# PCB_RX.net
KiCad netlist of a schematic drawn in Altium Designer
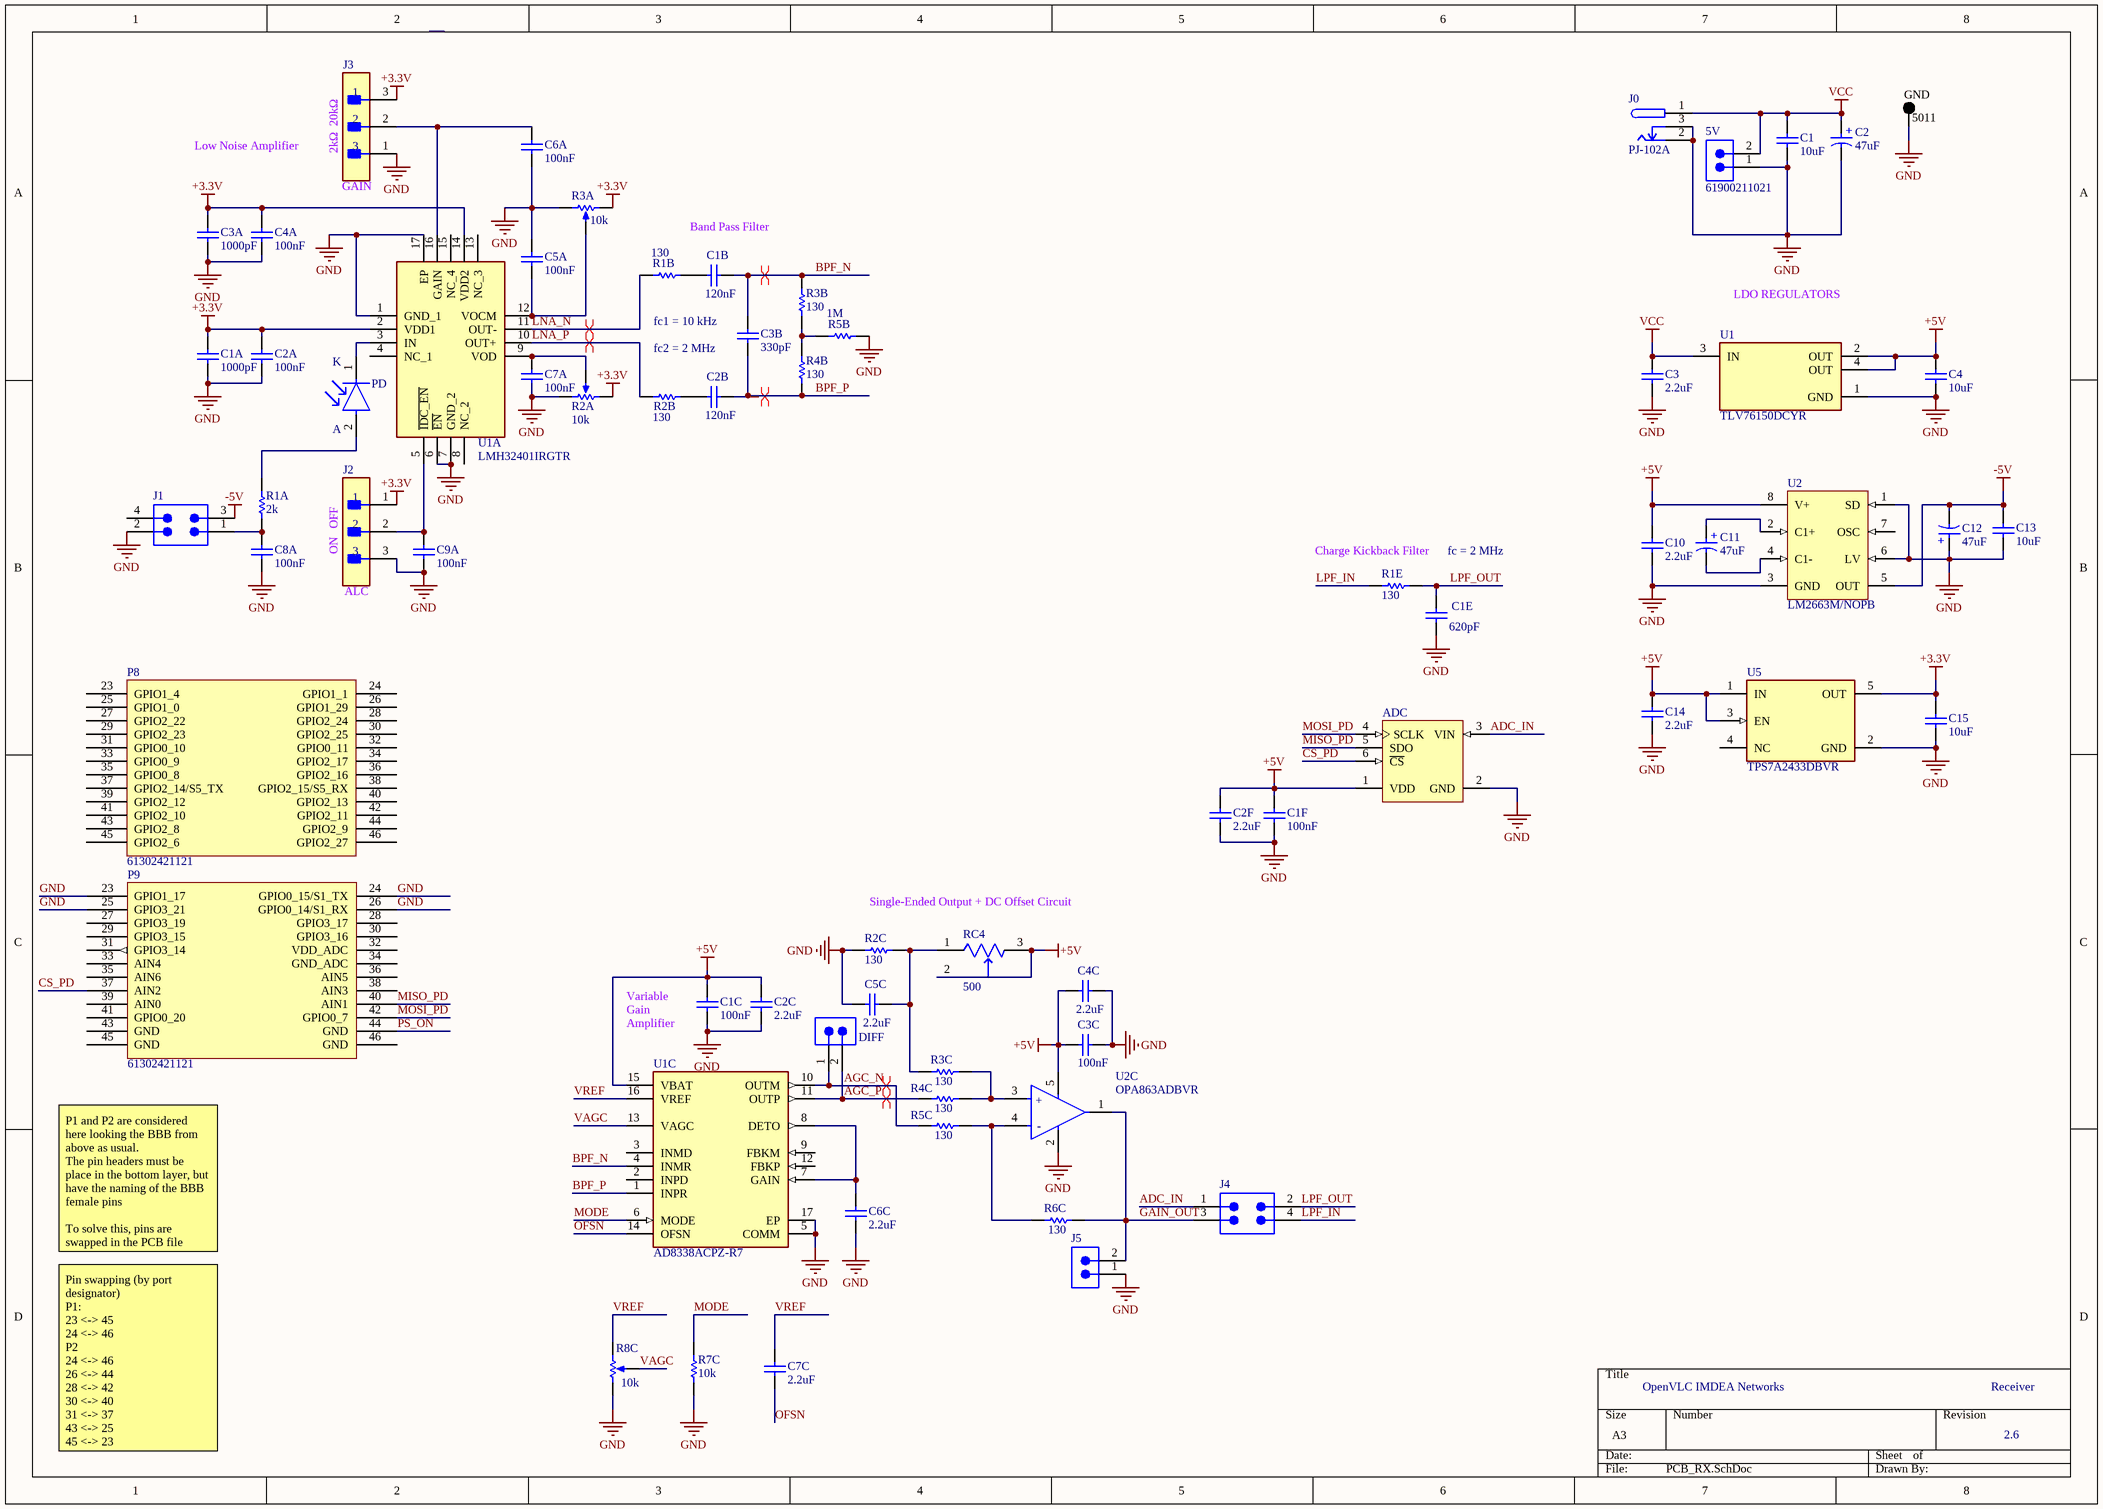
[diagram p0: PCB_RX.SchDoc]

(export (version "E")
  (design (tool "Eeschema 10.0.6"))
  (components
    (comp (ref "5V")
      (value "61900211021")
      (footprint "61900211021")
      (libsource (lib "Altium Content Vault") (part "Header_Male_1R_02P"))
    )
    (comp (ref "ADC")
      (value "ADS7886SBDBVR")
      (footprint "TI-DBV6_M")
      (fields (field (name "MANUFACTURER") "Texas Instruments"))
      (libsource (lib "Altium Content Vault") (part "TI-ADS788XDXX6"))
    )
    (comp (ref "C1")
      (value "10uF")
      (footprint "RESC1608X55N")
      (description "Capacitor")
      (fields (field (name "Comment") "Cap") (field (name "PUBLISHER") "Altium Limited"))
      (libsource (lib "Miscellaneous Devices") (part "Cap"))
    )
    (comp (ref "C1A")
      (value "1000pF")
      (footprint "RESC1608X55N")
      (description "Capacitor")
      (fields (field (name "Comment") "Cap") (field (name "PUBLISHER") "Altium Limited"))
      (libsource (lib "Miscellaneous Devices") (part "Cap"))
    )
    (comp (ref "C1B")
      (value "120nF")
      (footprint "RESC1608X55N")
      (description "Capacitor")
      (fields (field (name "Comment") "Cap") (field (name "PUBLISHER") "Altium Limited"))
      (libsource (lib "Miscellaneous Devices") (part "Cap"))
    )
    (comp (ref "C1C")
      (value "100nF")
      (footprint "RESC1608X55N")
      (description "Capacitor")
      (fields (field (name "Comment") "Cap") (field (name "PUBLISHER") "Altium Limited"))
      (libsource (lib "Miscellaneous Devices") (part "Cap"))
    )
    (comp (ref "C1E")
      (value "620pF")
      (footprint "RESC1608X55N")
      (description "Capacitor")
      (fields (field (name "Comment") "Cap") (field (name "PUBLISHER") "Altium Limited"))
      (libsource (lib "Miscellaneous Devices") (part "Cap"))
    )
    (comp (ref "C1F")
      (value "100nF")
      (footprint "RESC1608X55N")
      (description "Capacitor")
      (fields (field (name "Comment") "Cap") (field (name "PUBLISHER") "Altium Limited"))
      (libsource (lib "Miscellaneous Devices") (part "Cap"))
    )
    (comp (ref "C2")
      (value "47uF")
      (footprint "WCAP-PSLP_D5H5.5")
      (description "875105242006 WCAP-PSLP Aluminum Polymer Capacitors")
      (fields (field (name "TOLERANCE") "20%"))
      (libsource (lib "Altium Content Vault") (part "Capacitor_Polarized"))
    )
    (comp (ref "C2A")
      (value "100nF")
      (footprint "RESC1608X55N")
      (description "Capacitor")
      (fields (field (name "Comment") "Cap") (field (name "PUBLISHER") "Altium Limited"))
      (libsource (lib "Miscellaneous Devices") (part "Cap"))
    )
    (comp (ref "C2B")
      (value "120nF")
      (footprint "RESC1608X55N")
      (description "Capacitor")
      (fields (field (name "Comment") "Cap") (field (name "PUBLISHER") "Altium Limited"))
      (libsource (lib "Miscellaneous Devices") (part "Cap"))
    )
    (comp (ref "C2C")
      (value "2.2uF")
      (footprint "RESC1608X55N")
      (description "Capacitor")
      (fields (field (name "Comment") "Cap") (field (name "PUBLISHER") "Altium Limited"))
      (libsource (lib "Miscellaneous Devices") (part "Cap"))
    )
    (comp (ref "C2F")
      (value "2.2uF")
      (footprint "RESC1608X55N")
      (description "Capacitor")
      (fields (field (name "Comment") "Cap") (field (name "PUBLISHER") "Altium Limited"))
      (libsource (lib "Miscellaneous Devices") (part "Cap"))
    )
    (comp (ref "C3")
      (value "2.2uF")
      (footprint "RESC1608X55N")
      (description "Capacitor")
      (fields (field (name "Comment") "Cap") (field (name "PUBLISHER") "Altium Limited"))
      (libsource (lib "Miscellaneous Devices") (part "Cap"))
    )
    (comp (ref "C3A")
      (value "1000pF")
      (footprint "RESC1608X55N")
      (description "Capacitor")
      (fields (field (name "Comment") "Cap") (field (name "PUBLISHER") "Altium Limited"))
      (libsource (lib "Miscellaneous Devices") (part "Cap"))
    )
    (comp (ref "C3B")
      (value "330pF")
      (footprint "RESC1608X55N")
      (description "Capacitor")
      (fields (field (name "Comment") "Cap") (field (name "PUBLISHER") "Altium Limited"))
      (libsource (lib "Miscellaneous Devices") (part "Cap"))
    )
    (comp (ref "C3C")
      (value "100nF")
      (footprint "RESC1608X55N")
      (description "Capacitor")
      (fields (field (name "Comment") "Cap") (field (name "PUBLISHER") "Altium Limited"))
      (libsource (lib "Miscellaneous Devices") (part "Cap"))
    )
    (comp (ref "C4")
      (value "10uF")
      (footprint "RESC1608X55N")
      (description "Capacitor")
      (fields (field (name "Comment") "Cap") (field (name "PUBLISHER") "Altium Limited"))
      (libsource (lib "Miscellaneous Devices") (part "Cap"))
    )
    (comp (ref "C4A")
      (value "100nF")
      (footprint "RESC1608X55N")
      (description "Capacitor")
      (fields (field (name "Comment") "Cap") (field (name "PUBLISHER") "Altium Limited"))
      (libsource (lib "Miscellaneous Devices") (part "Cap"))
    )
    (comp (ref "C4C")
      (value "2.2uF")
      (footprint "RESC1608X55N")
      (description "Capacitor")
      (fields (field (name "Comment") "Cap") (field (name "PUBLISHER") "Altium Limited"))
      (libsource (lib "Miscellaneous Devices") (part "Cap"))
    )
    (comp (ref "C5A")
      (value "100nF")
      (footprint "RESC1608X55N")
      (description "Capacitor")
      (fields (field (name "Comment") "Cap") (field (name "PUBLISHER") "Altium Limited"))
      (libsource (lib "Miscellaneous Devices") (part "Cap"))
    )
    (comp (ref "C5C")
      (value "2.2uF")
      (footprint "RESC1608X55N")
      (description "Capacitor")
      (fields (field (name "Comment") "Cap") (field (name "PUBLISHER") "Altium Limited"))
      (libsource (lib "Miscellaneous Devices") (part "Cap"))
    )
    (comp (ref "C6A")
      (value "100nF")
      (footprint "RESC1608X55N")
      (description "Capacitor")
      (fields (field (name "Comment") "Cap") (field (name "PUBLISHER") "Altium Limited"))
      (libsource (lib "Miscellaneous Devices") (part "Cap"))
    )
    (comp (ref "C6C")
      (value "2.2uF")
      (footprint "RESC1608X55N")
      (description "Capacitor")
      (fields (field (name "Comment") "Cap") (field (name "PUBLISHER") "Altium Limited"))
      (libsource (lib "Miscellaneous Devices") (part "Cap"))
    )
    (comp (ref "C7A")
      (value "100nF")
      (footprint "RESC1608X55N")
      (description "Capacitor")
      (fields (field (name "Comment") "Cap") (field (name "PUBLISHER") "Altium Limited"))
      (libsource (lib "Miscellaneous Devices") (part "Cap"))
    )
    (comp (ref "C7C")
      (value "2.2uF")
      (footprint "RESC1608X55N")
      (description "Capacitor")
      (fields (field (name "Comment") "Cap") (field (name "PUBLISHER") "Altium Limited"))
      (libsource (lib "Miscellaneous Devices") (part "Cap"))
    )
    (comp (ref "C8A")
      (value "100nF")
      (footprint "RESC1608X55N")
      (description "Capacitor")
      (fields (field (name "Comment") "Cap") (field (name "PUBLISHER") "Altium Limited"))
      (libsource (lib "Miscellaneous Devices") (part "Cap"))
    )
    (comp (ref "C9A")
      (value "100nF")
      (footprint "RESC1608X55N")
      (description "Capacitor")
      (fields (field (name "Comment") "Cap") (field (name "PUBLISHER") "Altium Limited"))
      (libsource (lib "Miscellaneous Devices") (part "Cap"))
    )
    (comp (ref "C10")
      (value "2.2uF")
      (footprint "RESC1608X55N")
      (description "Capacitor")
      (fields (field (name "Comment") "Cap") (field (name "PUBLISHER") "Altium Limited"))
      (libsource (lib "Miscellaneous Devices") (part "Cap"))
    )
    (comp (ref "C11")
      (value "47uF")
      (footprint "WCAP-PSLP_D5H5.5")
      (description "875105242006 WCAP-PSLP Aluminum Polymer Capacitors")
      (fields (field (name "TOLERANCE") "20%"))
      (libsource (lib "Altium Content Vault") (part "Capacitor_Polarized"))
    )
    (comp (ref "C12")
      (value "47uF")
      (footprint "WCAP-PSLP_D5H5.5")
      (description "875105242006 WCAP-PSLP Aluminum Polymer Capacitors")
      (fields (field (name "TOLERANCE") "20%"))
      (libsource (lib "Altium Content Vault") (part "Capacitor_Polarized"))
    )
    (comp (ref "C13")
      (value "10uF")
      (footprint "RESC1608X55N")
      (description "Capacitor")
      (fields (field (name "Comment") "Cap") (field (name "PUBLISHER") "Altium Limited"))
      (libsource (lib "Miscellaneous Devices") (part "Cap"))
    )
    (comp (ref "C14")
      (value "2.2uF")
      (footprint "RESC1608X55N")
      (description "Capacitor")
      (fields (field (name "Comment") "GRM188R6YA475KE15D") (field (name "PUBLISHER") "Altium Limited"))
      (libsource (lib "Miscellaneous Devices") (part "Cap"))
    )
    (comp (ref "C15")
      (value "10uF")
      (footprint "RESC1608X55N")
      (description "Capacitor")
      (fields (field (name "Comment") "GRM188R6YA106MA73D") (field (name "PUBLISHER") "Altium Limited"))
      (libsource (lib "Miscellaneous Devices") (part "Cap"))
    )
    (comp (ref "DIFF")
      (value "61300211121")
      (footprint "61300211121")
      (libsource (lib "Altium Content Vault") (part "Header_Male_1R_02P"))
    )
    (comp (ref "GND")
      (value "5011")
      (footprint "KSTN-5011_V")
      (description "Test Point, Black, Through Hole, RoHS, Bulk")
      (fields (field (name "MANUFACTURER") "Keystone"))
      (libsource (lib "Altium Content Vault") (part "TESTPOINT_BLACK"))
    )
    (comp (ref "J0")
      (value "PJ-102A")
      (footprint "FP-PJ-102A-MFG")
      (description "PJ-102A 2.0 x 6.5 mm, 2.5 A, Horizontal, Through Hole, Tapered Pins, Dc Power Jack Connector")
      (libsource (lib "Altium Content Vault") (part "c639f672d24b5d70918fa8d934b95d1"))
    )
    (comp (ref "J1")
      (value "62200421121")
      (footprint "62200421121")
      (libsource (lib "Altium Content Vault") (part "Header_Male_2R_04P"))
    )
    (comp (ref "J2")
      (value "GRPB031VWVN-RC")
      (footprint "FP-TMS-103-02-G-S-MFG")
      (description "CONN HEADER VERT 3POS 1.27MM")
      (libsource (lib "") (part "0d3f023dd272f625e17a2be33dea85f_1"))
    )
    (comp (ref "J3")
      (value "61300311121")
      (footprint "FP-TMS-103-02-G-S-MFG")
      (description "CONN HEADER VERT 3POS 1.27MM")
      (libsource (lib "Altium Content Vault") (part "0d3f023dd272f625e17a2be33dea85f"))
    )
    (comp (ref "J4")
      (value "61300421121")
      (footprint "61300421121")
      (libsource (lib "Altium Content Vault") (part "Header_Male_2R_04P"))
    )
    (comp (ref "J5")
      (value "61900211121")
      (footprint "61900211121")
      (libsource (lib "Altium Content Vault") (part "Header_Male_1R_02P"))
    )
    (comp (ref "P8")
      (value "61302421121")
      (footprint "BBB_CAPE_NO_HEADER_R_24")
      (libsource (lib "BeagleBoneCape") (part "BBB_P8_reduced"))
    )
    (comp (ref "P9")
      (value "61302421121")
      (footprint "BBB_CAPE_NO_HEADER_R_24")
      (libsource (lib "BeagleBoneCape") (part "BBB_P9_reduced"))
    )
    (comp (ref "PD")
      (value "SFH213")
      (footprint "FP-SFH213-0")
      (description "SENSOR PHOTODIODE 850NM RADIAL")
      (fields (field (name "MANUFACTURER") "OSRAM") (field (name "VOLTAGE") "50V"))
      (libsource (lib "Altium Content Vault") (part "9b7c99953c265a88c20b8f1023d9605"))
    )
    (comp (ref "R1A")
      (value "2k")
      (footprint "RESC1608X55N")
      (description "Resistor")
      (fields (field (name "Comment") "Res1") (field (name "PUBLISHER") "Altium Limited"))
      (libsource (lib "Miscellaneous Devices") (part "Res1"))
    )
    (comp (ref "R1B")
      (value "130")
      (footprint "RESC1608X55N")
      (description "Resistor")
      (fields (field (name "Comment") "Res1") (field (name "PUBLISHER") "Altium Limited"))
      (libsource (lib "Miscellaneous Devices") (part "Res1"))
    )
    (comp (ref "R1E")
      (value "130")
      (footprint "RESC1608X55N")
      (description "Resistor")
      (fields (field (name "Comment") "Res1") (field (name "PUBLISHER") "Altium Limited"))
      (libsource (lib "Miscellaneous Devices") (part "Res1"))
    )
    (comp (ref "R2A")
      (value "10k")
      (footprint "BOUR-3362P")
      (description "Square Trimpot(R) Trimming Potentiometer, 10 KOhm, 300 V, -55 to 125 degC, 3-Pin THD, RoHS, Tube")
      (fields (field (name "TOLERANCE") "1%"))
      (libsource (lib "Altium Content Vault") (part "RES-POT-3"))
    )
    (comp (ref "R2B")
      (value "130")
      (footprint "RESC1608X55N")
      (description "Resistor")
      (fields (field (name "Comment") "Res1") (field (name "PUBLISHER") "Altium Limited"))
      (libsource (lib "Miscellaneous Devices") (part "Res1"))
    )
    (comp (ref "R2C")
      (value "130")
      (footprint "RESC1608X55N")
      (description "Resistor")
      (fields (field (name "Comment") "Res1") (field (name "PUBLISHER") "Altium Limited"))
      (libsource (lib "Miscellaneous Devices") (part "Res1"))
    )
    (comp (ref "R3A")
      (value "10k")
      (footprint "BOUR-3362P")
      (description "Square Trimpot(R) Trimming Potentiometer, 10 KOhm, 300 V, -55 to 125 degC, 3-Pin THD, RoHS, Tube")
      (fields (field (name "TOLERANCE") "1%"))
      (libsource (lib "Altium Content Vault") (part "RES-POT-3"))
    )
    (comp (ref "R3B")
      (value "130")
      (footprint "RESC1608X55N")
      (description "Resistor")
      (fields (field (name "Comment") "500") (field (name "PUBLISHER") "Altium Limited"))
      (libsource (lib "Miscellaneous Devices") (part "Res1"))
    )
    (comp (ref "R3C")
      (value "130")
      (footprint "RESC1608X55N")
      (description "Resistor")
      (fields (field (name "Comment") "Res1") (field (name "PUBLISHER") "Altium Limited"))
      (libsource (lib "Miscellaneous Devices") (part "Res1"))
    )
    (comp (ref "R4B")
      (value "130")
      (footprint "RESC1608X55N")
      (description "Resistor")
      (fields (field (name "Comment") "Res1") (field (name "PUBLISHER") "Altium Limited"))
      (libsource (lib "Miscellaneous Devices") (part "Res1"))
    )
    (comp (ref "R4C")
      (value "130")
      (footprint "RESC1608X55N")
      (description "Resistor")
      (fields (field (name "Comment") "Res1") (field (name "PUBLISHER") "Altium Limited"))
      (libsource (lib "Miscellaneous Devices") (part "Res1"))
    )
    (comp (ref "R5B")
      (value "1M")
      (footprint "RESC1608X55N")
      (description "Resistor")
      (fields (field (name "Comment") "Res1") (field (name "PUBLISHER") "Altium Limited"))
      (libsource (lib "Miscellaneous Devices") (part "Res1"))
    )
    (comp (ref "R5C")
      (value "130")
      (footprint "RESC1608X55N")
      (description "Resistor")
      (fields (field (name "Comment") "Res1") (field (name "PUBLISHER") "Altium Limited"))
      (libsource (lib "Miscellaneous Devices") (part "Res1"))
    )
    (comp (ref "R6C")
      (value "130")
      (footprint "RESC1608X55N")
      (description "Resistor")
      (fields (field (name "Comment") "Res1") (field (name "PUBLISHER") "Altium Limited"))
      (libsource (lib "Miscellaneous Devices") (part "Res1"))
    )
    (comp (ref "R7C")
      (value "10k")
      (footprint "RESC1608X55N")
      (description "Resistor")
      (fields (field (name "Comment") "Res1") (field (name "PUBLISHER") "Altium Limited"))
      (libsource (lib "Miscellaneous Devices") (part "Res1"))
    )
    (comp (ref "R8C")
      (value "10k")
      (footprint "BOUR-3362P")
      (description "Square Trimpot(R) Trimming Potentiometer, 10 KOhm, 300 V, -55 to 125 degC, 3-Pin THD, RoHS, Tube")
      (fields (field (name "TOLERANCE") "1%"))
      (libsource (lib "Altium Content Vault") (part "RES-POT-3"))
    )
    (comp (ref "RC4")
      (value "500")
      (footprint "FP-3296W-MFG")
      (description "TRIMMER 500K OHM 0.5W PC PIN TOP")
      (fields
        (field (name "MANUFACTURER") "Bourns")
        (field (name "OCTOPART") "https://octopart.com/3296w-1-504lf-bourns-143884")
      )
      (libsource (lib "Altium Content Vault") (part "8d460c8a6f7ec10b1759d1b9c49aa93"))
    )
    (comp (ref "U1")
      (value "TLV76150DCYR")
      (footprint "FP-DCY0004A-MFG")
      (description "TLV76150DCYR 1-A 16-V high-PSRR linear voltage regulator 4-SOT-223 -40 to 125")
      (libsource (lib "Altium Content Vault") (part "991ffb903c51cf6179ce9942c0606aa"))
    )
    (comp (ref "U1A")
      (value "LMH32401IRGTR")
      (footprint "QFN50P300X300X100-17N-D")
      (fields (field (name "MOUSER PART NUMBER") "595-LMH32401IRGTR"))
      (libsource (lib "LMH32401IRGTR") (part "LMH32401IRGTR"))
    )
    (comp (ref "U1C")
      (value "AD8338ACPZ-R7")
      (footprint "FP-CP-16-22-IPC_A")
      (description "IC OPAMP VGA 1 CIRCUIT 16LFCSP")
      (fields
        (field (name "OCTOPART") "https://octopart.com/ad8338acpz-r7-analog+devices-21054770")
        (field (name "MANUFACTURER") "Analog Devices")
      )
      (libsource (lib "Altium Content Vault") (part "4ce7887af0b7713ffabab50ab6d8fb3"))
    )
    (comp (ref "U2")
      (value "LM2663M/NOPB")
      (footprint "D0008A_N")
      (description "Switched Capacitor Voltage Converter, 8-pin Narrow SOIC, Pb-Free")
      (fields (field (name "MANUFACTURER") "Texas Instruments"))
      (libsource (lib "Altium Content Vault") (part "PM-CHP-LM2661M-8"))
    )
    (comp (ref "U2C")
      (value "OPA863ADBVR")
      (footprint "FP-DBV0005A-MFG")
      (libsource (lib "Altium Content Vault") (part "4cd2dec86d87e6d90761bbce91e6ba3"))
    )
    (comp (ref "U5")
      (value "TPS7A2433DBVR")
      (footprint "FP-DBV0005A-MFG")
      (libsource (lib "Altium Content Vault") (part "ee7747973c1ed1d4cccbb20406fa51c"))
    )
  )
  (nets
    (net (code "1") (name "+3.3V") (class "Default")
      (node (ref "C15") (pin "2") (pinfunction "2_2") (pintype "passive"))
      (node (ref "C1A") (pin "1") (pinfunction "1_1") (pintype "passive"))
      (node (ref "C2A") (pin "1") (pinfunction "1_1") (pintype "passive"))
      (node (ref "C3A") (pin "1") (pinfunction "1_1") (pintype "passive"))
      (node (ref "C4A") (pin "1") (pinfunction "1_1") (pintype "passive"))
      (node (ref "J2") (pin "1") (pinfunction "1_1") (pintype "passive"))
      (node (ref "J3") (pin "3") (pinfunction "3_3") (pintype "passive"))
      (node (ref "R2A") (pin "1") (pinfunction "CCW_1") (pintype "passive"))
      (node (ref "R3A") (pin "3") (pinfunction "CW_3") (pintype "passive"))
      (node (ref "U1A") (pin "14") (pinfunction "VDD2_14") (pintype "passive"))
      (node (ref "U1A") (pin "2") (pinfunction "VDD1_2") (pintype "passive"))
      (node (ref "U5") (pin "5") (pinfunction "OUT_5") (pintype "power_in"))
    )
    (net (code "2") (name "+5V") (class "Default")
      (node (ref "ADC") (pin "1") (pinfunction "VDD_1") (pintype "power_in"))
      (node (ref "C10") (pin "2") (pinfunction "2_2") (pintype "passive"))
      (node (ref "C14") (pin "2") (pinfunction "2_2") (pintype "passive"))
      (node (ref "C1C") (pin "1") (pinfunction "1_1") (pintype "passive"))
      (node (ref "C1F") (pin "1") (pinfunction "1_1") (pintype "passive"))
      (node (ref "C2C") (pin "1") (pinfunction "1_1") (pintype "passive"))
      (node (ref "C2F") (pin "1") (pinfunction "1_1") (pintype "passive"))
      (node (ref "C3C") (pin "1") (pinfunction "1_1") (pintype "passive"))
      (node (ref "C4") (pin "2") (pinfunction "2_2") (pintype "passive"))
      (node (ref "C4C") (pin "1") (pinfunction "1_1") (pintype "passive"))
      (node (ref "RC4") (pin "2") (pinfunction "WIPER_2") (pintype "passive"))
      (node (ref "RC4") (pin "3") (pinfunction "CW_3") (pintype "passive"))
      (node (ref "U1") (pin "2") (pinfunction "OUT_2") (pintype "passive"))
      (node (ref "U1") (pin "4") (pinfunction "OUT_4") (pintype "passive"))
      (node (ref "U1C") (pin "15") (pinfunction "VBAT_15") (pintype "power_in"))
      (node (ref "U2") (pin "8") (pinfunction "V+_8") (pintype "power_in"))
      (node (ref "U2C") (pin "5") (pinfunction "VS+_5") (pintype "power_in"))
      (node (ref "U5") (pin "1") (pinfunction "IN_1") (pintype "power_in"))
      (node (ref "U5") (pin "3") (pinfunction "EN_3") (pintype "input"))
    )
    (net (code "3") (name "-5V") (class "Default")
      (node (ref "C12") (pin "2") (pinfunction "N_2") (pintype "passive"))
      (node (ref "C13") (pin "2") (pinfunction "2_2") (pintype "passive"))
      (node (ref "J1") (pin "3") (pinfunction "3_3") (pintype "passive"))
      (node (ref "U2") (pin "5") (pinfunction "OUT_5") (pintype "power_in"))
    )
    (net (code "4") (name "/ADC_IN") (class "Default")
      (node (ref "ADC") (pin "3") (pinfunction "VIN_3") (pintype "input"))
      (node (ref "J4") (pin "1") (pinfunction "1_1") (pintype "passive"))
    )
    (net (code "5") (name "/AGC_N") (class "Default")
      (node (ref "DIFF") (pin "1") (pinfunction "1_1") (pintype "passive"))
      (node (ref "R5C") (pin "2") (pinfunction "2_2") (pintype "passive"))
      (node (ref "U1C") (pin "10") (pinfunction "OUTM_10") (pintype "output"))
    )
    (net (code "6") (name "/AGC_P") (class "Default")
      (node (ref "DIFF") (pin "2") (pinfunction "2_2") (pintype "passive"))
      (node (ref "R4C") (pin "2") (pinfunction "2_2") (pintype "passive"))
      (node (ref "U1C") (pin "11") (pinfunction "OUTP_11") (pintype "output"))
    )
    (net (code "7") (name "/BPF_N") (class "Default")
      (node (ref "C1B") (pin "2") (pinfunction "2_2") (pintype "passive"))
      (node (ref "C3B") (pin "2") (pinfunction "2_2") (pintype "passive"))
      (node (ref "R3B") (pin "1") (pinfunction "1_1") (pintype "passive"))
      (node (ref "U1C") (pin "4") (pinfunction "INMR_4") (pintype "passive"))
    )
    (net (code "8") (name "/BPF_P") (class "Default")
      (node (ref "C2B") (pin "2") (pinfunction "2_2") (pintype "passive"))
      (node (ref "C3B") (pin "1") (pinfunction "1_1") (pintype "passive"))
      (node (ref "R4B") (pin "2") (pinfunction "2_2") (pintype "passive"))
      (node (ref "U1C") (pin "1") (pinfunction "INPR_1") (pintype "passive"))
    )
    (net (code "9") (name "/CS_PD") (class "Default")
      (node (ref "ADC") (pin "6") (pinfunction "~{CS}_6") (pintype "input"))
      (node (ref "P9") (pin "37") (pinfunction "AIN2_37") (pintype "passive"))
    )
    (net (code "10") (name "/GAIN_OUT") (class "Default")
      (node (ref "J4") (pin "3") (pinfunction "3_3") (pintype "passive"))
      (node (ref "J5") (pin "2") (pinfunction "2_2") (pintype "passive"))
      (node (ref "R6C") (pin "1") (pinfunction "1_1") (pintype "passive"))
      (node (ref "U2C") (pin "1") (pinfunction "VOUT_1") (pintype "passive"))
    )
    (net (code "11") (name "/LNA_N") (class "Default")
      (node (ref "R1B") (pin "2") (pinfunction "2_2") (pintype "passive"))
      (node (ref "U1A") (pin "11") (pinfunction "OUT-_11") (pintype "passive"))
    )
    (net (code "12") (name "/LNA_P") (class "Default")
      (node (ref "R2B") (pin "2") (pinfunction "2_2") (pintype "passive"))
      (node (ref "U1A") (pin "10") (pinfunction "OUT+_10") (pintype "passive"))
    )
    (net (code "13") (name "/LPF_IN") (class "Default")
      (node (ref "J4") (pin "4") (pinfunction "4_4") (pintype "passive"))
      (node (ref "R1E") (pin "2") (pinfunction "2_2") (pintype "passive"))
    )
    (net (code "14") (name "/LPF_OUT") (class "Default")
      (node (ref "C1E") (pin "1") (pinfunction "1_1") (pintype "passive"))
      (node (ref "J4") (pin "2") (pinfunction "2_2") (pintype "passive"))
      (node (ref "R1E") (pin "1") (pinfunction "1_1") (pintype "passive"))
    )
    (net (code "15") (name "/MISO_PD") (class "Default")
      (node (ref "ADC") (pin "5") (pinfunction "SDO_5") (pintype "tri_state"))
      (node (ref "P9") (pin "40") (pinfunction "AIN1_40") (pintype "passive"))
    )
    (net (code "16") (name "/MODE") (class "Default")
      (node (ref "R7C") (pin "2") (pinfunction "2_2") (pintype "passive"))
      (node (ref "U1C") (pin "6") (pinfunction "MODE_6") (pintype "input"))
    )
    (net (code "17") (name "/MOSI_PD") (class "Default")
      (node (ref "ADC") (pin "4") (pinfunction "SCLK_4") (pintype "input"))
      (node (ref "P9") (pin "42") (pinfunction "GPIO0_7_42") (pintype "passive"))
    )
    (net (code "18") (name "/OFSN") (class "Default")
      (node (ref "C7C") (pin "1") (pinfunction "1_1") (pintype "passive"))
      (node (ref "U1C") (pin "14") (pinfunction "OFSN_14") (pintype "passive"))
    )
    (net (code "19") (name "/PS_ON") (class "Default")
      (node (ref "P9") (pin "44") (pinfunction "GND_44") (pintype "passive"))
    )
    (net (code "20") (name "/VAGC") (class "Default")
      (node (ref "R8C") (pin "2") (pinfunction "S_2") (pintype "passive"))
      (node (ref "U1C") (pin "13") (pinfunction "VAGC_13") (pintype "power_in"))
    )
    (net (code "21") (name "/VREF") (class "Default")
      (node (ref "C7C") (pin "2") (pinfunction "2_2") (pintype "passive"))
      (node (ref "R8C") (pin "3") (pinfunction "CW_3") (pintype "passive"))
      (node (ref "U1C") (pin "16") (pinfunction "VREF_16") (pintype "power_in"))
    )
    (net (code "22") (name "GND") (class "Default")
      (node (ref "5V") (pin "1") (pinfunction "1_1") (pintype "passive"))
      (node (ref "ADC") (pin "2") (pinfunction "GND_2") (pintype "power_in"))
      (node (ref "C1") (pin "2") (pinfunction "2_2") (pintype "passive"))
      (node (ref "C10") (pin "1") (pinfunction "1_1") (pintype "passive"))
      (node (ref "C12") (pin "1") (pinfunction "P_1") (pintype "passive"))
      (node (ref "C13") (pin "1") (pinfunction "1_1") (pintype "passive"))
      (node (ref "C14") (pin "1") (pinfunction "1_1") (pintype "passive"))
      (node (ref "C15") (pin "1") (pinfunction "1_1") (pintype "passive"))
      (node (ref "C1A") (pin "2") (pinfunction "2_2") (pintype "passive"))
      (node (ref "C1C") (pin "2") (pinfunction "2_2") (pintype "passive"))
      (node (ref "C1E") (pin "2") (pinfunction "2_2") (pintype "passive"))
      (node (ref "C1F") (pin "2") (pinfunction "2_2") (pintype "passive"))
      (node (ref "C2") (pin "2") (pinfunction "N_2") (pintype "passive"))
      (node (ref "C2A") (pin "2") (pinfunction "2_2") (pintype "passive"))
      (node (ref "C2C") (pin "2") (pinfunction "2_2") (pintype "passive"))
      (node (ref "C2F") (pin "2") (pinfunction "2_2") (pintype "passive"))
      (node (ref "C3") (pin "1") (pinfunction "1_1") (pintype "passive"))
      (node (ref "C3A") (pin "2") (pinfunction "2_2") (pintype "passive"))
      (node (ref "C3C") (pin "2") (pinfunction "2_2") (pintype "passive"))
      (node (ref "C4") (pin "1") (pinfunction "1_1") (pintype "passive"))
      (node (ref "C4A") (pin "2") (pinfunction "2_2") (pintype "passive"))
      (node (ref "C4C") (pin "2") (pinfunction "2_2") (pintype "passive"))
      (node (ref "C5A") (pin "1") (pinfunction "1_1") (pintype "passive"))
      (node (ref "C5C") (pin "1") (pinfunction "1_1") (pintype "passive"))
      (node (ref "C6A") (pin "2") (pinfunction "2_2") (pintype "passive"))
      (node (ref "C6C") (pin "1") (pinfunction "1_1") (pintype "passive"))
      (node (ref "C7A") (pin "2") (pinfunction "2_2") (pintype "passive"))
      (node (ref "C8A") (pin "1") (pinfunction "1_1") (pintype "passive"))
      (node (ref "C9A") (pin "2") (pinfunction "2_2") (pintype "passive"))
      (node (ref "GND") (pin "1") (pinfunction "1_1") (pintype "passive"))
      (node (ref "J0") (pin "2") (pinfunction "2_2") (pintype "passive"))
      (node (ref "J0") (pin "3") (pinfunction "3_3") (pintype "passive"))
      (node (ref "J1") (pin "2") (pinfunction "2_2") (pintype "passive"))
      (node (ref "J2") (pin "3") (pinfunction "3_3") (pintype "passive"))
      (node (ref "J3") (pin "1") (pinfunction "1_1") (pintype "passive"))
      (node (ref "J5") (pin "1") (pinfunction "1_1") (pintype "passive"))
      (node (ref "P9") (pin "23") (pinfunction "GPIO1_17_23") (pintype "passive"))
      (node (ref "P9") (pin "24") (pinfunction "GPIO0_15/S1_TX_24") (pintype "passive"))
      (node (ref "P9") (pin "25") (pinfunction "GPIO3_21_25") (pintype "passive"))
      (node (ref "P9") (pin "26") (pinfunction "GPIO0_14/S1_RX_26") (pintype "passive"))
      (node (ref "R2A") (pin "3") (pinfunction "CW_3") (pintype "passive"))
      (node (ref "R2C") (pin "2") (pinfunction "2_2") (pintype "passive"))
      (node (ref "R3A") (pin "1") (pinfunction "CCW_1") (pintype "passive"))
      (node (ref "R5B") (pin "1") (pinfunction "1_1") (pintype "passive"))
      (node (ref "R7C") (pin "1") (pinfunction "1_1") (pintype "passive"))
      (node (ref "R8C") (pin "1") (pinfunction "CCW_1") (pintype "passive"))
      (node (ref "U1") (pin "1") (pinfunction "GND_1") (pintype "power_in"))
      (node (ref "U1A") (pin "1") (pinfunction "GND_1_1") (pintype "passive"))
      (node (ref "U1A") (pin "17") (pinfunction "EP_17") (pintype "passive"))
      (node (ref "U1A") (pin "6") (pinfunction "~{EN}_6") (pintype "passive"))
      (node (ref "U1A") (pin "7") (pinfunction "GND_2_7") (pintype "passive"))
      (node (ref "U1C") (pin "17") (pinfunction "EP_17") (pintype "power_in"))
      (node (ref "U1C") (pin "5") (pinfunction "COMM_5") (pintype "power_in"))
      (node (ref "U2") (pin "1") (pinfunction "SD_1") (pintype "input"))
      (node (ref "U2") (pin "3") (pinfunction "GND_3") (pintype "power_in"))
      (node (ref "U2") (pin "6") (pinfunction "LV_6") (pintype "input"))
      (node (ref "U2C") (pin "2") (pinfunction "VS-_2") (pintype "power_in"))
      (node (ref "U5") (pin "2") (pinfunction "GND_2") (pintype "power_in"))
    )
    (net (code "23") (name "Net-(C1B-Pad1)") (class "Default")
      (node (ref "C1B") (pin "1") (pinfunction "1_1") (pintype "passive"))
      (node (ref "R1B") (pin "1") (pinfunction "1_1") (pintype "passive"))
    )
    (net (code "24") (name "Net-(C2B-Pad1)") (class "Default")
      (node (ref "C2B") (pin "1") (pinfunction "1_1") (pintype "passive"))
      (node (ref "R2B") (pin "1") (pinfunction "1_1") (pintype "passive"))
    )
    (net (code "25") (name "Net-(C8A-Pad2)") (class "Default")
      (node (ref "C8A") (pin "2") (pinfunction "2_2") (pintype "passive"))
      (node (ref "J1") (pin "1") (pinfunction "1_1") (pintype "passive"))
      (node (ref "R1A") (pin "2") (pinfunction "2_2") (pintype "passive"))
    )
    (net (code "26") (name "Net-(C11-N)") (class "Default")
      (node (ref "C11") (pin "2") (pinfunction "N_2") (pintype "passive"))
      (node (ref "U2") (pin "4") (pinfunction "C1-_4") (pintype "input"))
    )
    (net (code "27") (name "Net-(C11-P)") (class "Default")
      (node (ref "C11") (pin "1") (pinfunction "P_1") (pintype "passive"))
      (node (ref "U2") (pin "2") (pinfunction "C1+_2") (pintype "input"))
    )
    (net (code "28") (name "Net-(PD-A)") (class "Default")
      (node (ref "PD") (pin "2") (pinfunction "A_2") (pintype "passive"))
      (node (ref "R1A") (pin "1") (pinfunction "1_1") (pintype "passive"))
    )
    (net (code "29") (name "Net-(PD-C)") (class "Default")
      (node (ref "PD") (pin "1") (pinfunction "C_1") (pintype "passive"))
      (node (ref "U1A") (pin "3") (pinfunction "IN_3") (pintype "passive"))
    )
    (net (code "30") (name "Net-(R2A-S)") (class "Default")
      (node (ref "C7A") (pin "1") (pinfunction "1_1") (pintype "passive"))
      (node (ref "R2A") (pin "2") (pinfunction "S_2") (pintype "passive"))
      (node (ref "U1A") (pin "9") (pinfunction "VOD_9") (pintype "passive"))
    )
    (net (code "31") (name "Net-(R3A-S)") (class "Default")
      (node (ref "C5A") (pin "2") (pinfunction "2_2") (pintype "passive"))
      (node (ref "R3A") (pin "2") (pinfunction "S_2") (pintype "passive"))
      (node (ref "U1A") (pin "12") (pinfunction "VOCM_12") (pintype "passive"))
    )
    (net (code "32") (name "Net-(R3B-Pad2)") (class "Default")
      (node (ref "R3B") (pin "2") (pinfunction "2_2") (pintype "passive"))
      (node (ref "R4B") (pin "1") (pinfunction "1_1") (pintype "passive"))
      (node (ref "R5B") (pin "2") (pinfunction "2_2") (pintype "passive"))
    )
    (net (code "33") (name "Net-(RC4-CCW)") (class "Default")
      (node (ref "C5C") (pin "2") (pinfunction "2_2") (pintype "passive"))
      (node (ref "R2C") (pin "1") (pinfunction "1_1") (pintype "passive"))
      (node (ref "R3C") (pin "2") (pinfunction "2_2") (pintype "passive"))
      (node (ref "RC4") (pin "1") (pinfunction "CCW_1") (pintype "passive"))
    )
    (net (code "34") (name "Net-(U1A-GAIN)") (class "Default")
      (node (ref "C6A") (pin "1") (pinfunction "1_1") (pintype "passive"))
      (node (ref "J3") (pin "2") (pinfunction "2_2") (pintype "passive"))
      (node (ref "U1A") (pin "16") (pinfunction "GAIN_16") (pintype "passive"))
    )
    (net (code "35") (name "Net-(U1A-~{IDC_EN})") (class "Default")
      (node (ref "C9A") (pin "1") (pinfunction "1_1") (pintype "passive"))
      (node (ref "J2") (pin "2") (pinfunction "2_2") (pintype "passive"))
      (node (ref "U1A") (pin "5") (pinfunction "~{IDC_EN}_5") (pintype "passive"))
    )
    (net (code "36") (name "Net-(U1C-DETO)") (class "Default")
      (node (ref "C6C") (pin "2") (pinfunction "2_2") (pintype "passive"))
      (node (ref "U1C") (pin "7") (pinfunction "GAIN_7") (pintype "input"))
      (node (ref "U1C") (pin "8") (pinfunction "DETO_8") (pintype "output"))
    )
    (net (code "37") (name "Net-(U2C-VIN+)") (class "Default")
      (node (ref "R3C") (pin "1") (pinfunction "1_1") (pintype "passive"))
      (node (ref "R4C") (pin "1") (pinfunction "1_1") (pintype "passive"))
      (node (ref "U2C") (pin "3") (pinfunction "VIN+_3") (pintype "tri_state"))
    )
    (net (code "38") (name "Net-(U2C-VIN-)") (class "Default")
      (node (ref "R5C") (pin "1") (pinfunction "1_1") (pintype "passive"))
      (node (ref "R6C") (pin "2") (pinfunction "2_2") (pintype "passive"))
      (node (ref "U2C") (pin "4") (pinfunction "VIN-_4") (pintype "tri_state"))
    )
    (net (code "39") (name "VCC") (class "Default")
      (node (ref "5V") (pin "2") (pinfunction "2_2") (pintype "passive"))
      (node (ref "C1") (pin "1") (pinfunction "1_1") (pintype "passive"))
      (node (ref "C2") (pin "1") (pinfunction "P_1") (pintype "passive"))
      (node (ref "C3") (pin "2") (pinfunction "2_2") (pintype "passive"))
      (node (ref "J0") (pin "1") (pinfunction "1_1") (pintype "passive"))
      (node (ref "U1") (pin "3") (pinfunction "IN_3") (pintype "power_in"))
    )
    (net (code "40") (name "unconnected-(J1-Pad4)") (class "Default")
      (node (ref "J1") (pin "4") (pinfunction "4_4") (pintype "passive"))
    )
    (net (code "41") (name "unconnected-(P8-GPIO0_8-Pad35)") (class "Default")
      (node (ref "P8") (pin "35") (pinfunction "GPIO0_8_35") (pintype "passive"))
    )
    (net (code "42") (name "unconnected-(P8-GPIO0_9-Pad33)") (class "Default")
      (node (ref "P8") (pin "33") (pinfunction "GPIO0_9_33") (pintype "passive"))
    )
    (net (code "43") (name "unconnected-(P8-GPIO0_10-Pad31)") (class "Default")
      (node (ref "P8") (pin "31") (pinfunction "GPIO0_10_31") (pintype "passive"))
    )
    (net (code "44") (name "unconnected-(P8-GPIO0_11-Pad32)") (class "Default")
      (node (ref "P8") (pin "32") (pinfunction "GPIO0_11_32") (pintype "passive"))
    )
    (net (code "45") (name "unconnected-(P8-GPIO1_0-Pad25)") (class "Default")
      (node (ref "P8") (pin "25") (pinfunction "GPIO1_0_25") (pintype "passive"))
    )
    (net (code "46") (name "unconnected-(P8-GPIO1_1-Pad24)") (class "Default")
      (node (ref "P8") (pin "24") (pinfunction "GPIO1_1_24") (pintype "passive"))
    )
    (net (code "47") (name "unconnected-(P8-GPIO1_4-Pad23)") (class "Default")
      (node (ref "P8") (pin "23") (pinfunction "GPIO1_4_23") (pintype "passive"))
    )
    (net (code "48") (name "unconnected-(P8-GPIO1_29-Pad26)") (class "Default")
      (node (ref "P8") (pin "26") (pinfunction "GPIO1_29_26") (pintype "passive"))
    )
    (net (code "49") (name "unconnected-(P8-GPIO2_6-Pad45)") (class "Default")
      (node (ref "P8") (pin "45") (pinfunction "GPIO2_6_45") (pintype "passive"))
    )
    (net (code "50") (name "unconnected-(P8-GPIO2_8-Pad43)") (class "Default")
      (node (ref "P8") (pin "43") (pinfunction "GPIO2_8_43") (pintype "passive"))
    )
    (net (code "51") (name "unconnected-(P8-GPIO2_9-Pad44)") (class "Default")
      (node (ref "P8") (pin "44") (pinfunction "GPIO2_9_44") (pintype "passive"))
    )
    (net (code "52") (name "unconnected-(P8-GPIO2_10-Pad41)") (class "Default")
      (node (ref "P8") (pin "41") (pinfunction "GPIO2_10_41") (pintype "passive"))
    )
    (net (code "53") (name "unconnected-(P8-GPIO2_11-Pad42)") (class "Default")
      (node (ref "P8") (pin "42") (pinfunction "GPIO2_11_42") (pintype "passive"))
    )
    (net (code "54") (name "unconnected-(P8-GPIO2_12-Pad39)") (class "Default")
      (node (ref "P8") (pin "39") (pinfunction "GPIO2_12_39") (pintype "passive"))
    )
    (net (code "55") (name "unconnected-(P8-GPIO2_13-Pad40)") (class "Default")
      (node (ref "P8") (pin "40") (pinfunction "GPIO2_13_40") (pintype "passive"))
    )
    (net (code "56") (name "unconnected-(P8-GPIO2_14{slash}S5_TX-Pad37)") (class "Default")
      (node (ref "P8") (pin "37") (pinfunction "GPIO2_14/S5_TX_37") (pintype "passive"))
    )
    (net (code "57") (name "unconnected-(P8-GPIO2_15{slash}S5_RX-Pad38)") (class "Default")
      (node (ref "P8") (pin "38") (pinfunction "GPIO2_15/S5_RX_38") (pintype "passive"))
    )
    (net (code "58") (name "unconnected-(P8-GPIO2_16-Pad36)") (class "Default")
      (node (ref "P8") (pin "36") (pinfunction "GPIO2_16_36") (pintype "passive"))
    )
    (net (code "59") (name "unconnected-(P8-GPIO2_17-Pad34)") (class "Default")
      (node (ref "P8") (pin "34") (pinfunction "GPIO2_17_34") (pintype "passive"))
    )
    (net (code "60") (name "unconnected-(P8-GPIO2_22-Pad27)") (class "Default")
      (node (ref "P8") (pin "27") (pinfunction "GPIO2_22_27") (pintype "passive"))
    )
    (net (code "61") (name "unconnected-(P8-GPIO2_23-Pad29)") (class "Default")
      (node (ref "P8") (pin "29") (pinfunction "GPIO2_23_29") (pintype "passive"))
    )
    (net (code "62") (name "unconnected-(P8-GPIO2_24-Pad28)") (class "Default")
      (node (ref "P8") (pin "28") (pinfunction "GPIO2_24_28") (pintype "passive"))
    )
    (net (code "63") (name "unconnected-(P8-GPIO2_25-Pad30)") (class "Default")
      (node (ref "P8") (pin "30") (pinfunction "GPIO2_25_30") (pintype "passive"))
    )
    (net (code "64") (name "unconnected-(P8-GPIO2_27-Pad46)") (class "Default")
      (node (ref "P8") (pin "46") (pinfunction "GPIO2_27_46") (pintype "passive"))
    )
    (net (code "65") (name "unconnected-(P9-AIN0-Pad39)") (class "Default")
      (node (ref "P9") (pin "39") (pinfunction "AIN0_39") (pintype "passive"))
    )
    (net (code "66") (name "unconnected-(P9-AIN3-Pad38)") (class "Default")
      (node (ref "P9") (pin "38") (pinfunction "AIN3_38") (pintype "passive"))
    )
    (net (code "67") (name "unconnected-(P9-AIN4-Pad33)") (class "Default")
      (node (ref "P9") (pin "33") (pinfunction "AIN4_33") (pintype "passive"))
    )
    (net (code "68") (name "unconnected-(P9-AIN5-Pad36)") (class "Default")
      (node (ref "P9") (pin "36") (pinfunction "AIN5_36") (pintype "passive"))
    )
    (net (code "69") (name "unconnected-(P9-AIN6-Pad35)") (class "Default")
      (node (ref "P9") (pin "35") (pinfunction "AIN6_35") (pintype "passive"))
    )
    (net (code "70") (name "unconnected-(P9-GND-Pad43)") (class "Default")
      (node (ref "P9") (pin "43") (pinfunction "GND_43") (pintype "passive"))
    )
    (net (code "71") (name "unconnected-(P9-GND-Pad45)") (class "Default")
      (node (ref "P9") (pin "45") (pinfunction "GND_45") (pintype "passive"))
    )
    (net (code "72") (name "unconnected-(P9-GND-Pad46)") (class "Default")
      (node (ref "P9") (pin "46") (pinfunction "GND_46") (pintype "passive"))
    )
    (net (code "73") (name "unconnected-(P9-GND_ADC-Pad34)") (class "Default")
      (node (ref "P9") (pin "34") (pinfunction "GND_ADC_34") (pintype "passive"))
    )
    (net (code "74") (name "unconnected-(P9-GPIO0_20-Pad41)") (class "Default")
      (node (ref "P9") (pin "41") (pinfunction "GPIO0_20_41") (pintype "passive"))
    )
    (net (code "75") (name "unconnected-(P9-GPIO3_14-Pad31)") (class "Default")
      (node (ref "P9") (pin "31") (pinfunction "GPIO3_14_31") (pintype "output"))
    )
    (net (code "76") (name "unconnected-(P9-GPIO3_15-Pad29)") (class "Default")
      (node (ref "P9") (pin "29") (pinfunction "GPIO3_15_29") (pintype "passive"))
    )
    (net (code "77") (name "unconnected-(P9-GPIO3_16-Pad30)") (class "Default")
      (node (ref "P9") (pin "30") (pinfunction "GPIO3_16_30") (pintype "passive"))
    )
    (net (code "78") (name "unconnected-(P9-GPIO3_17-Pad28)") (class "Default")
      (node (ref "P9") (pin "28") (pinfunction "GPIO3_17_28") (pintype "passive"))
    )
    (net (code "79") (name "unconnected-(P9-GPIO3_19-Pad27)") (class "Default")
      (node (ref "P9") (pin "27") (pinfunction "GPIO3_19_27") (pintype "passive"))
    )
    (net (code "80") (name "unconnected-(P9-VDD_ADC-Pad32)") (class "Default")
      (node (ref "P9") (pin "32") (pinfunction "VDD_ADC_32") (pintype "passive"))
    )
    (net (code "81") (name "unconnected-(U1A-NC_1-Pad4)") (class "Default")
      (node (ref "U1A") (pin "4") (pinfunction "NC_1_4") (pintype "passive"))
    )
    (net (code "82") (name "unconnected-(U1A-NC_2-Pad8)") (class "Default")
      (node (ref "U1A") (pin "8") (pinfunction "NC_2_8") (pintype "passive"))
    )
    (net (code "83") (name "unconnected-(U1A-NC_3-Pad13)") (class "Default")
      (node (ref "U1A") (pin "13") (pinfunction "NC_3_13") (pintype "passive"))
    )
    (net (code "84") (name "unconnected-(U1A-NC_4-Pad15)") (class "Default")
      (node (ref "U1A") (pin "15") (pinfunction "NC_4_15") (pintype "passive"))
    )
    (net (code "85") (name "unconnected-(U1C-FBKM-Pad9)") (class "Default")
      (node (ref "U1C") (pin "9") (pinfunction "FBKM_9") (pintype "input"))
    )
    (net (code "86") (name "unconnected-(U1C-FBKP-Pad12)") (class "Default")
      (node (ref "U1C") (pin "12") (pinfunction "FBKP_12") (pintype "input"))
    )
    (net (code "87") (name "unconnected-(U1C-INMD-Pad3)") (class "Default")
      (node (ref "U1C") (pin "3") (pinfunction "INMD_3") (pintype "passive"))
    )
    (net (code "88") (name "unconnected-(U1C-INPD-Pad2)") (class "Default")
      (node (ref "U1C") (pin "2") (pinfunction "INPD_2") (pintype "passive"))
    )
    (net (code "89") (name "unconnected-(U2-OSC-Pad7)") (class "Default")
      (node (ref "U2") (pin "7") (pinfunction "OSC_7") (pintype "input"))
    )
    (net (code "90") (name "unconnected-(U5-NC-Pad4)") (class "Default")
      (node (ref "U5") (pin "4") (pinfunction "NC_4") (pintype "passive"))
    )
  )
)
